# Nav.net
KiCad netlist of a schematic drawn in EAGLE
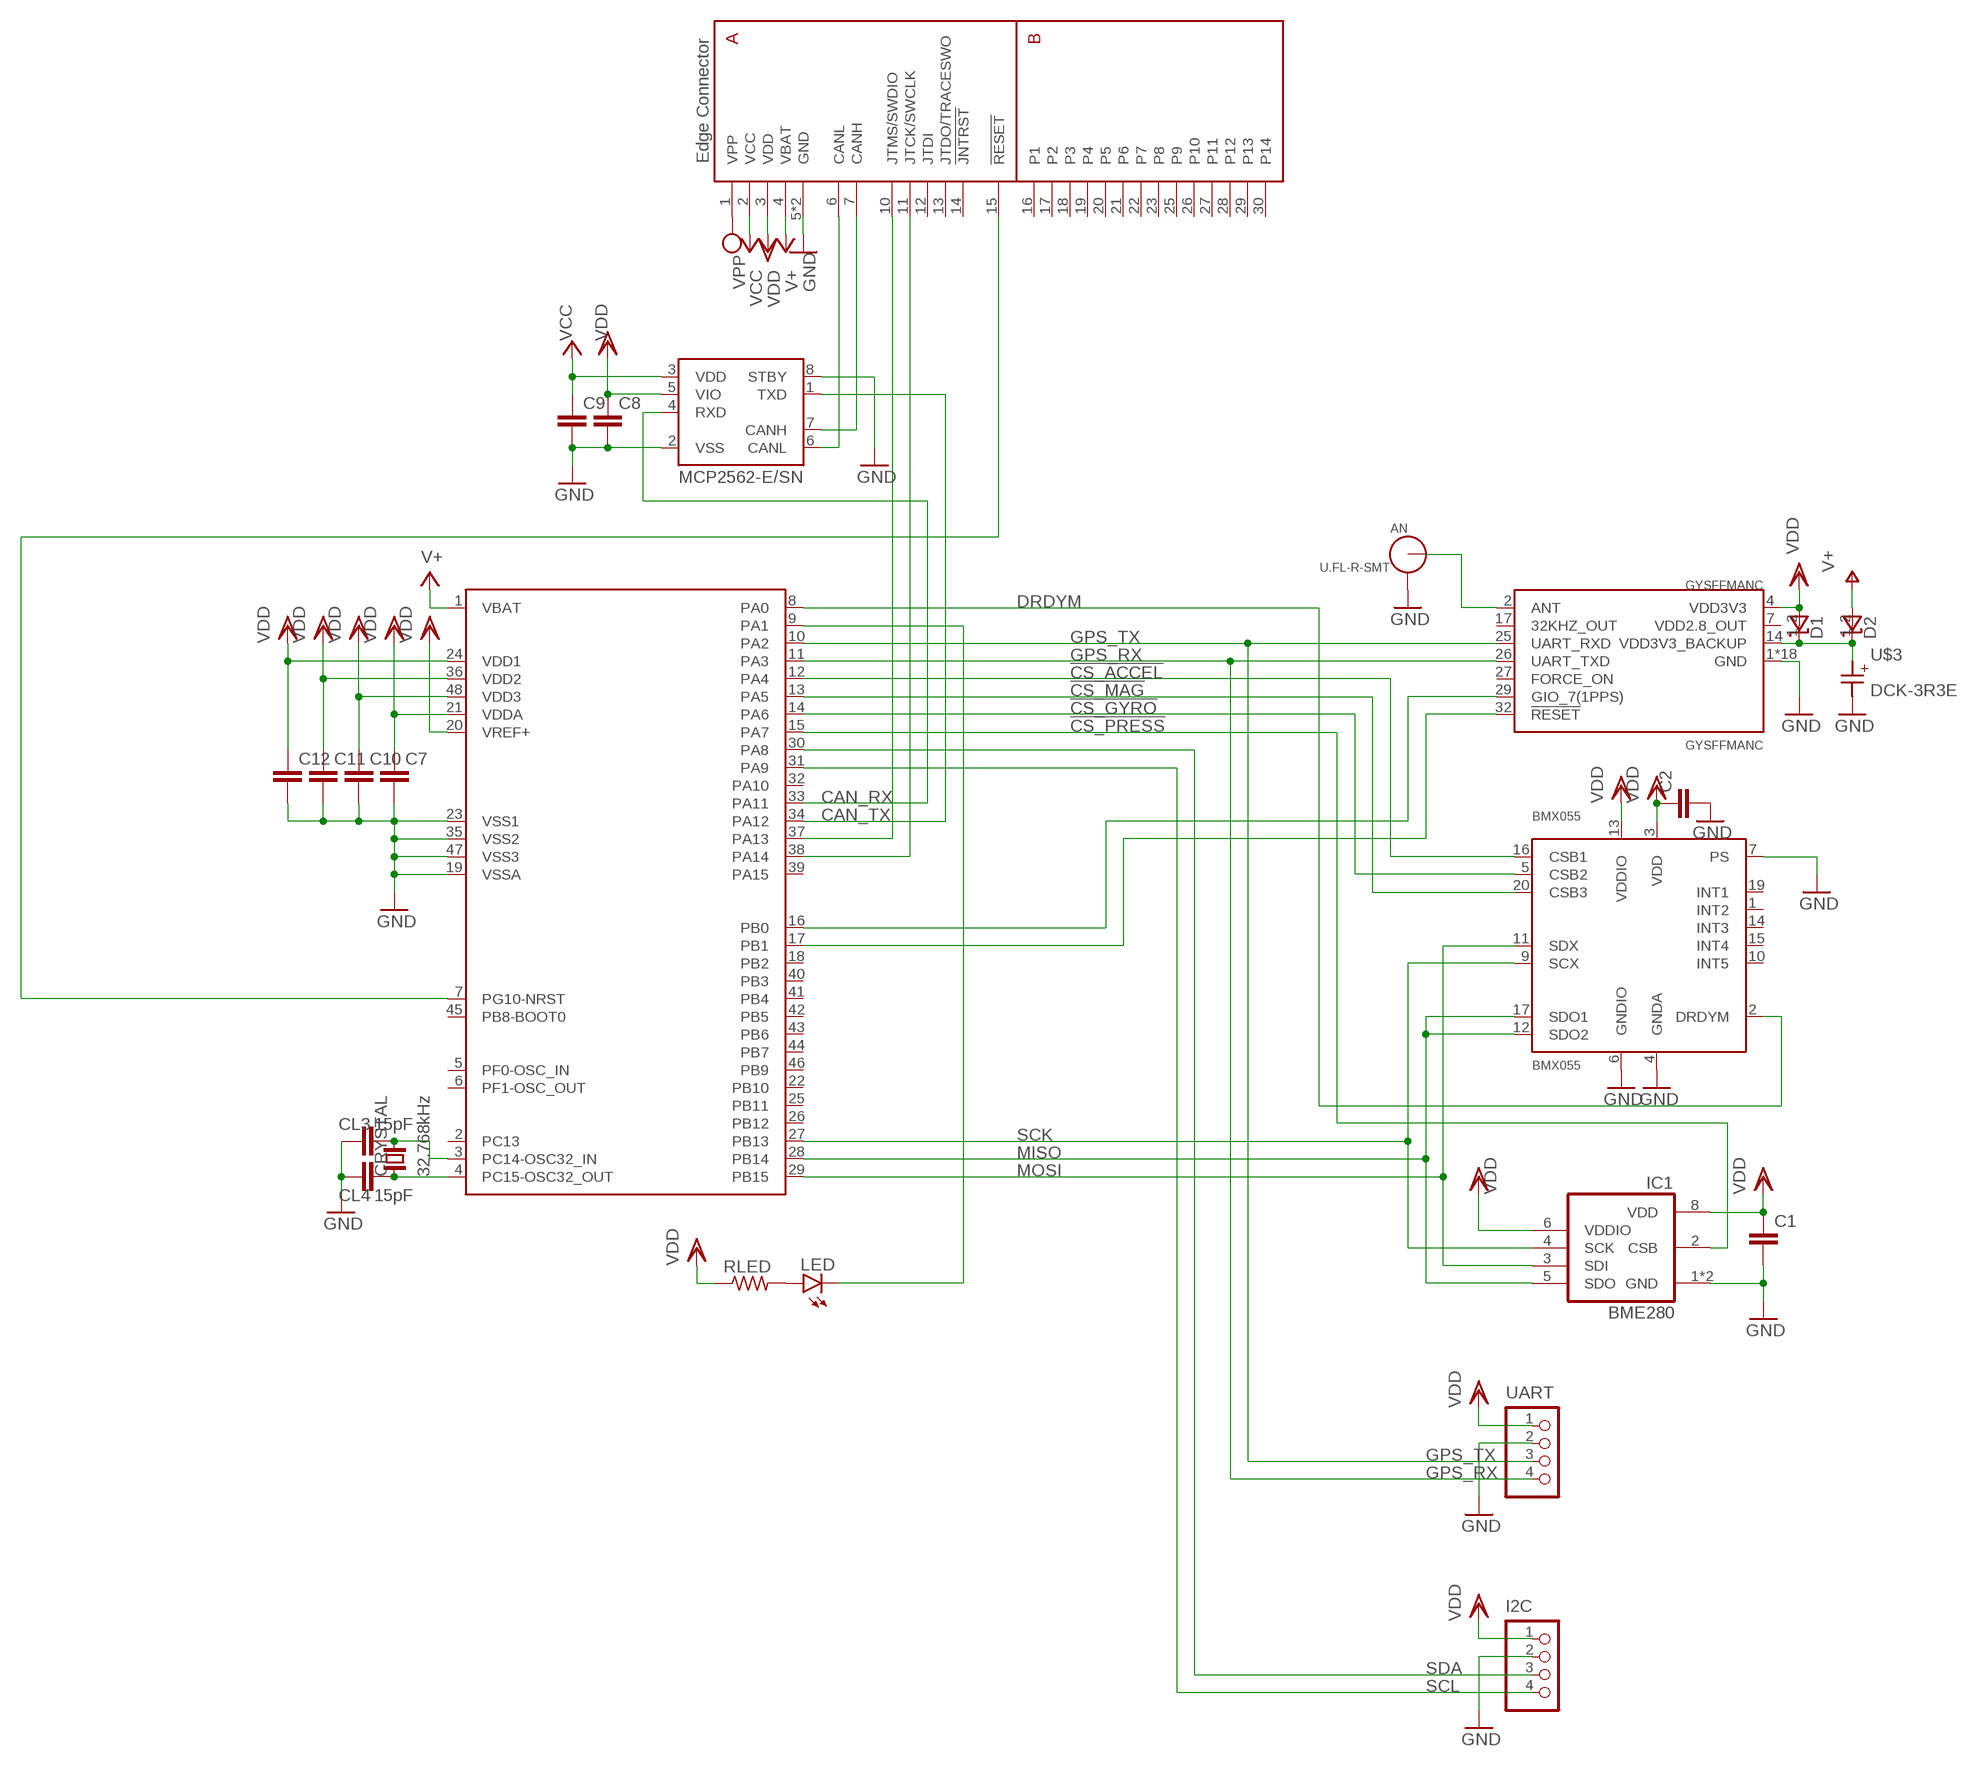
[diagram p0: schematic, sheet 1]

(export (version "E")
  (design (tool "Eeschema 10.0.6"))
  (components
    (comp (ref "AN")
      (value "U.FL-R-SMT")
      (footprint "eagle-import:U.FL_SMT")
      (fields (field (name "MANUFACTURER") "Hirose") (field (name "MPN") "U.FL-R-SMT-1(01)"))
      (libsource (lib "eagle-import") (part "U.FL-R-SMT"))
    )
    (comp (ref "BMX055")
      (value "BMX055")
      (footprint "eagle-import:BMX055")
      (fields (field (name "DIGI-KEY_PART_NUMBER") "828-1060-1-ND") (field (name "MF") "Bosch Sensortec"))
      (libsource (lib "eagle-import") (part "BMX055"))
    )
    (comp (ref "C1")
      (value "C-EUC0603K")
      (footprint "eagle-import:C0603K")
      (libsource (lib "eagle-import") (part "C-EUC0603K"))
    )
    (comp (ref "C2")
      (value "C-EUC0603K")
      (footprint "eagle-import:C0603K")
      (libsource (lib "eagle-import") (part "C-EUC0603K"))
    )
    (comp (ref "C7")
      (value "C-EUC0603K")
      (footprint "eagle-import:C0603K")
      (libsource (lib "eagle-import") (part "C-EUC0603K"))
    )
    (comp (ref "C8")
      (value "C-EUC0603K")
      (footprint "eagle-import:C0603K")
      (libsource (lib "eagle-import") (part "C-EUC0603K"))
    )
    (comp (ref "C9")
      (value "C-EUC0603K")
      (footprint "eagle-import:C0603K")
      (libsource (lib "eagle-import") (part "C-EUC0603K"))
    )
    (comp (ref "C10")
      (value "C-EUC0603K")
      (footprint "eagle-import:C0603K")
      (libsource (lib "eagle-import") (part "C-EUC0603K"))
    )
    (comp (ref "C11")
      (value "C-EUC0603K")
      (footprint "eagle-import:C0603K")
      (libsource (lib "eagle-import") (part "C-EUC0603K"))
    )
    (comp (ref "C12")
      (value "C-EUC0603K")
      (footprint "eagle-import:C0603K")
      (libsource (lib "eagle-import") (part "C-EUC0603K"))
    )
    (comp (ref "CL3")
      (value "15pF")
      (footprint "eagle-import:C0603K")
      (libsource (lib "eagle-import") (part "C-EUC0603K"))
    )
    (comp (ref "CL4")
      (value "15pF")
      (footprint "eagle-import:C0603K")
      (libsource (lib "eagle-import") (part "C-EUC0603K"))
    )
    (comp (ref "CRYSTAL")
      (value "32.768kHz")
      (footprint "eagle-import:FC-255")
      (libsource (lib "eagle-import") (part "CRYTALFC-255"))
    )
    (comp (ref "D1")
      (value "RB521S-30TE61")
      (footprint "eagle-import:SODFL1608X70N")
      (fields
        (field (name "MOUSER_PART_NUMBER") "755-RB521S-30TE61")
        (field (name "RS_PART_NUMBER") "0178677")
      )
      (libsource (lib "eagle-import") (part "RB521S-30TE61"))
    )
    (comp (ref "D2")
      (value "RB521S-30TE61")
      (footprint "eagle-import:SODFL1608X70N")
      (fields
        (field (name "MOUSER_PART_NUMBER") "755-RB521S-30TE61")
        (field (name "RS_PART_NUMBER") "0178677")
      )
      (libsource (lib "eagle-import") (part "RB521S-30TE61"))
    )
    (comp (ref "GYSFFMANC")
      (value "GYSFFMANC")
      (footprint "eagle-import:GYSFFMANC")
      (libsource (lib "eagle-import") (part "GYSFFMANC"))
    )
    (comp (ref "I2C")
      (value "S4B-PH-K-S")
      (footprint "eagle-import:S4B-PH-K-S")
      (libsource (lib "eagle-import") (part "S4B-PH-K-S"))
    )
    (comp (ref "IC1")
      (value "BME280")
      (footprint "eagle-import:BME280")
      (libsource (lib "eagle-import") (part "BME280"))
    )
    (comp (ref "LED")
      (value "LEDCHIP-LED0603")
      (footprint "eagle-import:CHIP-LED0603")
      (libsource (lib "eagle-import") (part "LEDCHIP-LED0603"))
    )
    (comp (ref "MCP2562")
      (value "MCP2562-E/SN")
      (footprint "eagle-import:SOIC127P600X175-8N")
      (fields (field (name "MF") "Microchip"))
      (libsource (lib "eagle-import") (part "MCP2562-E/SN"))
    )
    (comp (ref "RLED")
      (value "R-US_R0603")
      (footprint "eagle-import:R0603")
      (libsource (lib "eagle-import") (part "R-US_R0603"))
    )
    (comp (ref "U$1")
      (value "STM32G431-LQFP48")
      (footprint "eagle-import:LQFP48")
      (libsource (lib "eagle-import") (part "STM32G431-LQFP48"))
    )
    (comp (ref "U$2")
      (value "EDGE30")
      (footprint "eagle-import:EDGE30")
      (libsource (lib "eagle-import") (part "EDGE30"))
    )
    (comp (ref "U$3")
      (value "DCK-3R3E")
      (footprint "eagle-import:DC,DCK")
      (libsource (lib "eagle-import") (part "DCK-3R3E"))
    )
    (comp (ref "UART")
      (value "S4B-PH-K-S")
      (footprint "eagle-import:S4B-PH-K-S")
      (libsource (lib "eagle-import") (part "S4B-PH-K-S"))
    )
  )
  (nets
    (net (code "1") (name "/CAN_RX") (class "Default")
      (node (ref "MCP2562") (pin "4") (pinfunction "RXD_4") (pintype "output"))
      (node (ref "U$1") (pin "33") (pinfunction "PA11_33") (pintype "bidirectional"))
    )
    (net (code "2") (name "/CAN_TX") (class "Default")
      (node (ref "MCP2562") (pin "1") (pinfunction "TXD_1") (pintype "input"))
      (node (ref "U$1") (pin "34") (pinfunction "PA12_34") (pintype "bidirectional"))
    )
    (net (code "3") (name "/DRDYM") (class "Default")
      (node (ref "BMX055") (pin "2") (pinfunction "DRDYM_2") (pintype "bidirectional"))
      (node (ref "U$1") (pin "8") (pinfunction "PA0_8") (pintype "bidirectional"))
    )
    (net (code "4") (name "/GPS_RX") (class "Default")
      (node (ref "GYSFFMANC") (pin "26") (pinfunction "UART_TXD_26") (pintype "output"))
      (node (ref "U$1") (pin "11") (pinfunction "PA3_11") (pintype "bidirectional"))
      (node (ref "UART") (pin "4") (pinfunction "4_4") (pintype "passive"))
    )
    (net (code "5") (name "/GPS_TX") (class "Default")
      (node (ref "GYSFFMANC") (pin "25") (pinfunction "UART_RXD_25") (pintype "input"))
      (node (ref "U$1") (pin "10") (pinfunction "PA2_10") (pintype "bidirectional"))
      (node (ref "UART") (pin "3") (pinfunction "3_3") (pintype "passive"))
    )
    (net (code "6") (name "/MISO") (class "Default")
      (node (ref "BMX055") (pin "12") (pinfunction "SDO2_12") (pintype "bidirectional"))
      (node (ref "BMX055") (pin "17") (pinfunction "SDO1_17") (pintype "bidirectional"))
      (node (ref "IC1") (pin "5") (pinfunction "SDO_5") (pintype "input"))
      (node (ref "U$1") (pin "28") (pinfunction "PB14_28") (pintype "bidirectional"))
    )
    (net (code "7") (name "/MOSI") (class "Default")
      (node (ref "BMX055") (pin "11") (pinfunction "SDX_11") (pintype "bidirectional"))
      (node (ref "IC1") (pin "3") (pinfunction "SDI_3") (pintype "bidirectional"))
      (node (ref "U$1") (pin "29") (pinfunction "PB15_29") (pintype "bidirectional"))
    )
    (net (code "8") (name "/SCK") (class "Default")
      (node (ref "BMX055") (pin "9") (pinfunction "SCX_9") (pintype "bidirectional"))
      (node (ref "IC1") (pin "4") (pinfunction "SCK_4") (pintype "bidirectional"))
      (node (ref "U$1") (pin "27") (pinfunction "PB13_27") (pintype "bidirectional"))
    )
    (net (code "9") (name "/SCL") (class "Default")
      (node (ref "I2C") (pin "4") (pinfunction "4_4") (pintype "passive"))
      (node (ref "U$1") (pin "31") (pinfunction "PA9_31") (pintype "bidirectional"))
    )
    (net (code "10") (name "/SDA") (class "Default")
      (node (ref "I2C") (pin "3") (pinfunction "3_3") (pintype "passive"))
      (node (ref "U$1") (pin "30") (pinfunction "PA8_30") (pintype "bidirectional"))
    )
    (net (code "11") (name "/VDD2.8_OUT") (class "Default")
      (node (ref "GYSFFMANC") (pin "7") (pinfunction "VDD2.8_OUT_7") (pintype "power_in"))
    )
    (net (code "12") (name "/~{CS_ACCEL}") (class "Default")
      (node (ref "BMX055") (pin "16") (pinfunction "CSB1_16") (pintype "bidirectional"))
      (node (ref "U$1") (pin "12") (pinfunction "PA4_12") (pintype "bidirectional"))
    )
    (net (code "13") (name "/~{CS_GYRO}") (class "Default")
      (node (ref "BMX055") (pin "5") (pinfunction "CSB2_5") (pintype "bidirectional"))
      (node (ref "U$1") (pin "14") (pinfunction "PA6_14") (pintype "bidirectional"))
    )
    (net (code "14") (name "/~{CS_MAG}") (class "Default")
      (node (ref "BMX055") (pin "20") (pinfunction "CSB3_20") (pintype "bidirectional"))
      (node (ref "U$1") (pin "13") (pinfunction "PA5_13") (pintype "bidirectional"))
    )
    (net (code "15") (name "/~{CS_PRESS}") (class "Default")
      (node (ref "IC1") (pin "2") (pinfunction "CSB_2") (pintype "input"))
      (node (ref "U$1") (pin "15") (pinfunction "PA7_15") (pintype "bidirectional"))
    )
    (net (code "16") (name "GND") (class "Default")
      (node (ref "AN") (pin "GND1") (pinfunction "P$2_GND1") (pintype "bidirectional"))
      (node (ref "AN") (pin "GND2") (pinfunction "P$2_GND2") (pintype "bidirectional"))
      (node (ref "BMX055") (pin "4") (pinfunction "GNDA_4") (pintype "bidirectional"))
      (node (ref "BMX055") (pin "6") (pinfunction "GNDIO_6") (pintype "bidirectional"))
      (node (ref "BMX055") (pin "7") (pinfunction "PS_7") (pintype "bidirectional"))
      (node (ref "C1") (pin "2") (pinfunction "2_2") (pintype "passive"))
      (node (ref "C10") (pin "2") (pinfunction "2_2") (pintype "passive"))
      (node (ref "C11") (pin "2") (pinfunction "2_2") (pintype "passive"))
      (node (ref "C12") (pin "2") (pinfunction "2_2") (pintype "passive"))
      (node (ref "C2") (pin "2") (pinfunction "2_2") (pintype "passive"))
      (node (ref "C7") (pin "2") (pinfunction "2_2") (pintype "passive"))
      (node (ref "C8") (pin "2") (pinfunction "2_2") (pintype "passive"))
      (node (ref "C9") (pin "2") (pinfunction "2_2") (pintype "passive"))
      (node (ref "CL3") (pin "1") (pinfunction "1_1") (pintype "passive"))
      (node (ref "CL4") (pin "1") (pinfunction "1_1") (pintype "passive"))
      (node (ref "GYSFFMANC") (pin "1") (pinfunction "GND_1") (pintype "power_in"))
      (node (ref "GYSFFMANC") (pin "10") (pinfunction "GND_10") (pintype "power_in"))
      (node (ref "GYSFFMANC") (pin "12") (pinfunction "GND_12") (pintype "power_in"))
      (node (ref "GYSFFMANC") (pin "22") (pinfunction "GND_22") (pintype "power_in"))
      (node (ref "GYSFFMANC") (pin "3") (pinfunction "GND_3") (pintype "power_in"))
      (node (ref "GYSFFMANC") (pin "33") (pinfunction "GND_33") (pintype "power_in"))
      (node (ref "GYSFFMANC") (pin "36") (pinfunction "GND_36") (pintype "power_in"))
      (node (ref "GYSFFMANC") (pin "37") (pinfunction "GND_37") (pintype "power_in"))
      (node (ref "GYSFFMANC") (pin "38") (pinfunction "GND_38") (pintype "power_in"))
      (node (ref "GYSFFMANC") (pin "39") (pinfunction "GND_39") (pintype "power_in"))
      (node (ref "GYSFFMANC") (pin "40") (pinfunction "GND_40") (pintype "power_in"))
      (node (ref "GYSFFMANC") (pin "41") (pinfunction "GND_41") (pintype "power_in"))
      (node (ref "GYSFFMANC") (pin "42") (pinfunction "GND_42") (pintype "power_in"))
      (node (ref "GYSFFMANC") (pin "43") (pinfunction "GND_43") (pintype "power_in"))
      (node (ref "GYSFFMANC") (pin "44") (pinfunction "GND_44") (pintype "power_in"))
      (node (ref "GYSFFMANC") (pin "45") (pinfunction "GND_45") (pintype "power_in"))
      (node (ref "GYSFFMANC") (pin "46") (pinfunction "GND_46") (pintype "power_in"))
      (node (ref "GYSFFMANC") (pin "8") (pinfunction "GND_8") (pintype "power_in"))
      (node (ref "I2C") (pin "2") (pinfunction "2_2") (pintype "passive"))
      (node (ref "IC1") (pin "1") (pinfunction "GND_1") (pintype "power_in"))
      (node (ref "IC1") (pin "7") (pinfunction "GND_7") (pintype "power_in"))
      (node (ref "MCP2562") (pin "2") (pinfunction "VSS_2") (pintype "power_in"))
      (node (ref "MCP2562") (pin "8") (pinfunction "STBY_8") (pintype "input"))
      (node (ref "U$1") (pin "19") (pinfunction "VSSA_19") (pintype "bidirectional"))
      (node (ref "U$1") (pin "23") (pinfunction "VSS1_23") (pintype "bidirectional"))
      (node (ref "U$1") (pin "35") (pinfunction "VSS2_35") (pintype "bidirectional"))
      (node (ref "U$1") (pin "47") (pinfunction "VSS3_47") (pintype "bidirectional"))
      (node (ref "U$2") (pin "5") (pinfunction "GND_5") (pintype "power_in"))
      (node (ref "U$2") (pin "8") (pinfunction "GND_8") (pintype "power_in"))
      (node (ref "U$3") (pin "-") (pinfunction "-_-") (pintype "bidirectional"))
      (node (ref "UART") (pin "2") (pinfunction "2_2") (pintype "passive"))
    )
    (net (code "17") (name "Net-(AN-ANT)") (class "Default")
      (node (ref "AN") (pin "SIG") (pinfunction "ANT_SIG") (pintype "bidirectional"))
      (node (ref "GYSFFMANC") (pin "2") (pinfunction "ANT_2") (pintype "input"))
    )
    (net (code "18") (name "Net-(D1-K)") (class "Default")
      (node (ref "D1") (pin "1") (pinfunction "K_1") (pintype "bidirectional"))
      (node (ref "D2") (pin "1") (pinfunction "K_1") (pintype "bidirectional"))
      (node (ref "GYSFFMANC") (pin "14") (pinfunction "VDD3V3_BACKUP_14") (pintype "power_in"))
      (node (ref "U$3") (pin "+") (pinfunction "+_+") (pintype "bidirectional"))
    )
    (net (code "19") (name "Net-(GYSFFMANC-GIO_7(1PPS))") (class "Default")
      (node (ref "GYSFFMANC") (pin "29") (pinfunction "GIO_7(1PPS)_29") (pintype "bidirectional"))
      (node (ref "U$1") (pin "16") (pinfunction "PB0_16") (pintype "bidirectional"))
    )
    (net (code "20") (name "Net-(GYSFFMANC-~{RESET})") (class "Default")
      (node (ref "GYSFFMANC") (pin "32") (pinfunction "~{RESET}_32") (pintype "input"))
      (node (ref "U$1") (pin "17") (pinfunction "PB1_17") (pintype "bidirectional"))
    )
    (net (code "21") (name "Net-(LED-PadA)") (class "Default")
      (node (ref "LED") (pin "A") (pinfunction "A_A") (pintype "passive"))
      (node (ref "RLED") (pin "2") (pinfunction "2_2") (pintype "passive"))
    )
    (net (code "22") (name "Net-(MCP2562-CANH)") (class "Default")
      (node (ref "MCP2562") (pin "7") (pinfunction "CANH_7") (pintype "input"))
      (node (ref "U$2") (pin "7") (pinfunction "CANH_7") (pintype "bidirectional"))
    )
    (net (code "23") (name "Net-(MCP2562-CANL)") (class "Default")
      (node (ref "MCP2562") (pin "6") (pinfunction "CANL_6") (pintype "input"))
      (node (ref "U$2") (pin "6") (pinfunction "CANL_6") (pintype "bidirectional"))
    )
    (net (code "24") (name "Net-(U$1-PA1)") (class "Default")
      (node (ref "LED") (pin "C") (pinfunction "C_C") (pintype "passive"))
      (node (ref "U$1") (pin "9") (pinfunction "PA1_9") (pintype "bidirectional"))
    )
    (net (code "25") (name "Net-(U$1-PA13)") (class "Default")
      (node (ref "U$1") (pin "37") (pinfunction "PA13_37") (pintype "bidirectional"))
      (node (ref "U$2") (pin "10") (pinfunction "JTMS/SWDIO_10") (pintype "bidirectional"))
    )
    (net (code "26") (name "Net-(U$1-PA14)") (class "Default")
      (node (ref "U$1") (pin "38") (pinfunction "PA14_38") (pintype "bidirectional"))
      (node (ref "U$2") (pin "11") (pinfunction "JTCK/SWCLK_11") (pintype "bidirectional"))
    )
    (net (code "27") (name "Net-(U$1-PC14-OSC32_IN)") (class "Default")
      (node (ref "CL3") (pin "2") (pinfunction "2_2") (pintype "passive"))
      (node (ref "CRYSTAL") (pin "2") (pinfunction "2_2") (pintype "passive"))
      (node (ref "U$1") (pin "3") (pinfunction "PC14-OSC32_IN_3") (pintype "bidirectional"))
    )
    (net (code "28") (name "Net-(U$1-PC15-OSC32_OUT)") (class "Default")
      (node (ref "CL4") (pin "2") (pinfunction "2_2") (pintype "passive"))
      (node (ref "CRYSTAL") (pin "1") (pinfunction "1_1") (pintype "passive"))
      (node (ref "U$1") (pin "4") (pinfunction "PC15-OSC32_OUT_4") (pintype "bidirectional"))
    )
    (net (code "29") (name "Net-(U$1-PG10-NRST)") (class "Default")
      (node (ref "U$1") (pin "7") (pinfunction "PG10-NRST_7") (pintype "bidirectional"))
      (node (ref "U$2") (pin "15") (pinfunction "~{RESET}_15") (pintype "bidirectional"))
    )
    (net (code "30") (name "V+") (class "Default")
      (node (ref "D2") (pin "2") (pinfunction "A_2") (pintype "bidirectional"))
      (node (ref "U$1") (pin "1") (pinfunction "VBAT_1") (pintype "bidirectional"))
      (node (ref "U$2") (pin "4") (pinfunction "VBAT_4") (pintype "power_in"))
    )
    (net (code "31") (name "VCC") (class "Default")
      (node (ref "C9") (pin "1") (pinfunction "1_1") (pintype "passive"))
      (node (ref "MCP2562") (pin "3") (pinfunction "VDD_3") (pintype "power_in"))
      (node (ref "U$2") (pin "2") (pinfunction "VCC_2") (pintype "power_in"))
    )
    (net (code "32") (name "VDD") (class "Default")
      (node (ref "BMX055") (pin "13") (pinfunction "VDDIO_13") (pintype "bidirectional"))
      (node (ref "BMX055") (pin "3") (pinfunction "VDD_3") (pintype "bidirectional"))
      (node (ref "C1") (pin "1") (pinfunction "1_1") (pintype "passive"))
      (node (ref "C10") (pin "1") (pinfunction "1_1") (pintype "passive"))
      (node (ref "C11") (pin "1") (pinfunction "1_1") (pintype "passive"))
      (node (ref "C12") (pin "1") (pinfunction "1_1") (pintype "passive"))
      (node (ref "C2") (pin "1") (pinfunction "1_1") (pintype "passive"))
      (node (ref "C7") (pin "1") (pinfunction "1_1") (pintype "passive"))
      (node (ref "C8") (pin "1") (pinfunction "1_1") (pintype "passive"))
      (node (ref "D1") (pin "2") (pinfunction "A_2") (pintype "bidirectional"))
      (node (ref "GYSFFMANC") (pin "4") (pinfunction "VDD3V3_4") (pintype "power_in"))
      (node (ref "I2C") (pin "1") (pinfunction "1_1") (pintype "passive"))
      (node (ref "IC1") (pin "6") (pinfunction "VDDIO_6") (pintype "power_in"))
      (node (ref "IC1") (pin "8") (pinfunction "VDD_8") (pintype "power_in"))
      (node (ref "MCP2562") (pin "5") (pinfunction "VIO_5") (pintype "power_in"))
      (node (ref "RLED") (pin "1") (pinfunction "1_1") (pintype "passive"))
      (node (ref "U$1") (pin "20") (pinfunction "VREF+_20") (pintype "bidirectional"))
      (node (ref "U$1") (pin "21") (pinfunction "VDDA_21") (pintype "bidirectional"))
      (node (ref "U$1") (pin "24") (pinfunction "VDD1_24") (pintype "bidirectional"))
      (node (ref "U$1") (pin "36") (pinfunction "VDD2_36") (pintype "bidirectional"))
      (node (ref "U$1") (pin "48") (pinfunction "VDD3_48") (pintype "bidirectional"))
      (node (ref "U$2") (pin "3") (pinfunction "VDD_3") (pintype "power_in"))
      (node (ref "UART") (pin "1") (pinfunction "1_1") (pintype "passive"))
    )
    (net (code "33") (name "VPP") (class "Default")
      (node (ref "U$2") (pin "1") (pinfunction "VPP_1") (pintype "power_in"))
    )
    (net (code "34") (name "unconnected-(BMX055-INT1-Pad19)") (class "Default")
      (node (ref "BMX055") (pin "19") (pinfunction "INT1_19") (pintype "bidirectional"))
    )
    (net (code "35") (name "unconnected-(BMX055-INT2-Pad1)") (class "Default")
      (node (ref "BMX055") (pin "1") (pinfunction "INT2_1") (pintype "bidirectional"))
    )
    (net (code "36") (name "unconnected-(BMX055-INT3-Pad14)") (class "Default")
      (node (ref "BMX055") (pin "14") (pinfunction "INT3_14") (pintype "bidirectional"))
    )
    (net (code "37") (name "unconnected-(BMX055-INT4-Pad15)") (class "Default")
      (node (ref "BMX055") (pin "15") (pinfunction "INT4_15") (pintype "bidirectional"))
    )
    (net (code "38") (name "unconnected-(BMX055-INT5-Pad10)") (class "Default")
      (node (ref "BMX055") (pin "10") (pinfunction "INT5_10") (pintype "bidirectional"))
    )
    (net (code "39") (name "unconnected-(GYSFFMANC-32KHZ_OUT-Pad17)") (class "Default")
      (node (ref "GYSFFMANC") (pin "17") (pinfunction "32KHZ_OUT_17") (pintype "output"))
    )
    (net (code "40") (name "unconnected-(GYSFFMANC-FORCE_ON-Pad27)") (class "Default")
      (node (ref "GYSFFMANC") (pin "27") (pinfunction "FORCE_ON_27") (pintype "input"))
    )
    (net (code "41") (name "unconnected-(U$1-PA10-Pad32)") (class "Default")
      (node (ref "U$1") (pin "32") (pinfunction "PA10_32") (pintype "bidirectional"))
    )
    (net (code "42") (name "unconnected-(U$1-PA15-Pad39)") (class "Default")
      (node (ref "U$1") (pin "39") (pinfunction "PA15_39") (pintype "bidirectional"))
    )
    (net (code "43") (name "unconnected-(U$1-PB2-Pad18)") (class "Default")
      (node (ref "U$1") (pin "18") (pinfunction "PB2_18") (pintype "bidirectional"))
    )
    (net (code "44") (name "unconnected-(U$1-PB3-Pad40)") (class "Default")
      (node (ref "U$1") (pin "40") (pinfunction "PB3_40") (pintype "bidirectional"))
    )
    (net (code "45") (name "unconnected-(U$1-PB4-Pad41)") (class "Default")
      (node (ref "U$1") (pin "41") (pinfunction "PB4_41") (pintype "bidirectional"))
    )
    (net (code "46") (name "unconnected-(U$1-PB5-Pad42)") (class "Default")
      (node (ref "U$1") (pin "42") (pinfunction "PB5_42") (pintype "bidirectional"))
    )
    (net (code "47") (name "unconnected-(U$1-PB6-Pad43)") (class "Default")
      (node (ref "U$1") (pin "43") (pinfunction "PB6_43") (pintype "bidirectional"))
    )
    (net (code "48") (name "unconnected-(U$1-PB7-Pad44)") (class "Default")
      (node (ref "U$1") (pin "44") (pinfunction "PB7_44") (pintype "bidirectional"))
    )
    (net (code "49") (name "unconnected-(U$1-PB8-BOOT0-Pad45)") (class "Default")
      (node (ref "U$1") (pin "45") (pinfunction "PB8-BOOT0_45") (pintype "bidirectional"))
    )
    (net (code "50") (name "unconnected-(U$1-PB9-Pad46)") (class "Default")
      (node (ref "U$1") (pin "46") (pinfunction "PB9_46") (pintype "bidirectional"))
    )
    (net (code "51") (name "unconnected-(U$1-PB10-Pad22)") (class "Default")
      (node (ref "U$1") (pin "22") (pinfunction "PB10_22") (pintype "bidirectional"))
    )
    (net (code "52") (name "unconnected-(U$1-PB11-Pad25)") (class "Default")
      (node (ref "U$1") (pin "25") (pinfunction "PB11_25") (pintype "bidirectional"))
    )
    (net (code "53") (name "unconnected-(U$1-PB12-Pad26)") (class "Default")
      (node (ref "U$1") (pin "26") (pinfunction "PB12_26") (pintype "bidirectional"))
    )
    (net (code "54") (name "unconnected-(U$1-PC13-Pad2)") (class "Default")
      (node (ref "U$1") (pin "2") (pinfunction "PC13_2") (pintype "bidirectional"))
    )
    (net (code "55") (name "unconnected-(U$1-PF0-OSC_IN-Pad5)") (class "Default")
      (node (ref "U$1") (pin "5") (pinfunction "PF0-OSC_IN_5") (pintype "bidirectional"))
    )
    (net (code "56") (name "unconnected-(U$1-PF1-OSC_OUT-Pad6)") (class "Default")
      (node (ref "U$1") (pin "6") (pinfunction "PF1-OSC_OUT_6") (pintype "bidirectional"))
    )
    (net (code "57") (name "unconnected-(U$2-JTDI-Pad12)") (class "Default")
      (node (ref "U$2") (pin "12") (pinfunction "JTDI_12") (pintype "bidirectional"))
    )
    (net (code "58") (name "unconnected-(U$2-JTDO{slash}TRACESWO-Pad13)") (class "Default")
      (node (ref "U$2") (pin "13") (pinfunction "JTDO/TRACESWO_13") (pintype "bidirectional"))
    )
    (net (code "59") (name "unconnected-(U$2-P1-Pad16)") (class "Default")
      (node (ref "U$2") (pin "16") (pinfunction "P1_16") (pintype "bidirectional"))
    )
    (net (code "60") (name "unconnected-(U$2-P2-Pad17)") (class "Default")
      (node (ref "U$2") (pin "17") (pinfunction "P2_17") (pintype "bidirectional"))
    )
    (net (code "61") (name "unconnected-(U$2-P3-Pad18)") (class "Default")
      (node (ref "U$2") (pin "18") (pinfunction "P3_18") (pintype "bidirectional"))
    )
    (net (code "62") (name "unconnected-(U$2-P4-Pad19)") (class "Default")
      (node (ref "U$2") (pin "19") (pinfunction "P4_19") (pintype "bidirectional"))
    )
    (net (code "63") (name "unconnected-(U$2-P5-Pad20)") (class "Default")
      (node (ref "U$2") (pin "20") (pinfunction "P5_20") (pintype "bidirectional"))
    )
    (net (code "64") (name "unconnected-(U$2-P6-Pad21)") (class "Default")
      (node (ref "U$2") (pin "21") (pinfunction "P6_21") (pintype "bidirectional"))
    )
    (net (code "65") (name "unconnected-(U$2-P7-Pad22)") (class "Default")
      (node (ref "U$2") (pin "22") (pinfunction "P7_22") (pintype "bidirectional"))
    )
    (net (code "66") (name "unconnected-(U$2-P8-Pad23)") (class "Default")
      (node (ref "U$2") (pin "23") (pinfunction "P8_23") (pintype "bidirectional"))
    )
    (net (code "67") (name "unconnected-(U$2-P9-Pad25)") (class "Default")
      (node (ref "U$2") (pin "25") (pinfunction "P9_25") (pintype "bidirectional"))
    )
    (net (code "68") (name "unconnected-(U$2-P10-Pad26)") (class "Default")
      (node (ref "U$2") (pin "26") (pinfunction "P10_26") (pintype "bidirectional"))
    )
    (net (code "69") (name "unconnected-(U$2-P11-Pad27)") (class "Default")
      (node (ref "U$2") (pin "27") (pinfunction "P11_27") (pintype "bidirectional"))
    )
    (net (code "70") (name "unconnected-(U$2-P12-Pad28)") (class "Default")
      (node (ref "U$2") (pin "28") (pinfunction "P12_28") (pintype "bidirectional"))
    )
    (net (code "71") (name "unconnected-(U$2-P13-Pad29)") (class "Default")
      (node (ref "U$2") (pin "29") (pinfunction "P13_29") (pintype "bidirectional"))
    )
    (net (code "72") (name "unconnected-(U$2-P14-Pad30)") (class "Default")
      (node (ref "U$2") (pin "30") (pinfunction "P14_30") (pintype "bidirectional"))
    )
    (net (code "73") (name "unconnected-(U$2-~{JNTRST}-Pad14)") (class "Default")
      (node (ref "U$2") (pin "14") (pinfunction "~{JNTRST}_14") (pintype "bidirectional"))
    )
  )
)
